# LCD_KEY.net
KiCad netlist of a schematic drawn in Altium Designer
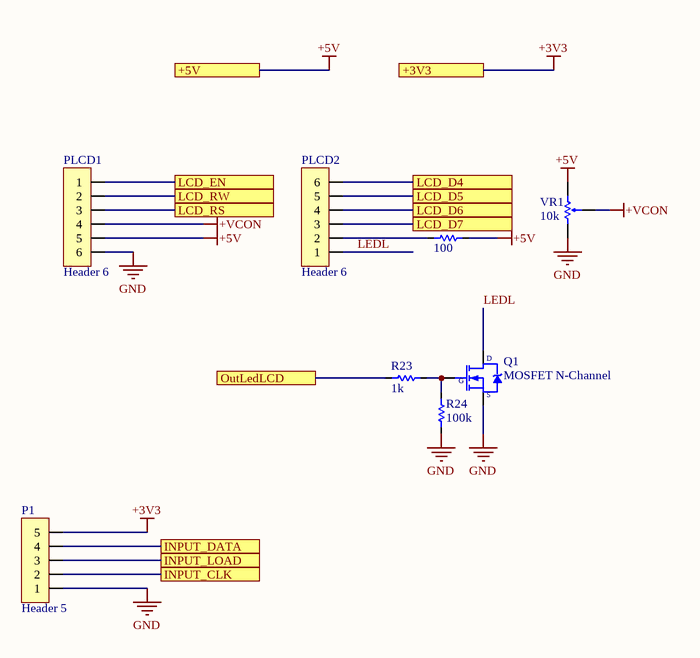
[diagram p0: LCD_KEY.SchDoc]

(export (version "E")
  (design (tool "Eeschema 10.0.6"))
  (components
    (comp (ref "P1")
      (value "Header 5")
      (footprint "Header 5")
      (description "Header, 5-Pin")
      (fields (field (name "PUBLISHER") "Altium Limited"))
      (libsource (lib "BKIT4U_LIB") (part "Header 5"))
    )
    (comp (ref "PLCD1")
      (value "Header 6")
      (footprint "XH2.54-6P")
      (description "Header, 6-Pin")
      (libsource (lib "BKIT4U_LIB_NEW") (part "Header 6"))
    )
    (comp (ref "PLCD2")
      (value "Header 6")
      (footprint "XH2.54-6P")
      (description "Header, 6-Pin")
      (libsource (lib "") (part "Header 6_1"))
    )
    (comp (ref "Q1")
      (value "MOSFET N-Channel")
      (footprint "SOT-23")
      (libsource (lib "BKIT4U_LIB_NEW") (part "MOSFET N-Channel"))
    )
    (comp (ref "R22")
      (value "100")
      (footprint "R 0603 (1608)")
      (description "Resistor")
      (fields (field (name "PUBLISHER") "Altium Limited"))
      (libsource (lib "BKIT4U_LIB_NEW") (part "Resistor"))
    )
    (comp (ref "R23")
      (value "1k")
      (footprint "R 0603 (1608)")
      (description "Resistor")
      (fields (field (name "PUBLISHER") "Altium Limited"))
      (libsource (lib "BKIT4U_LIB_NEW") (part "Resistor"))
    )
    (comp (ref "R24")
      (value "100k")
      (footprint "R 0603 (1608)")
      (description "Resistor")
      (fields (field (name "PUBLISHER") "Altium Limited"))
      (libsource (lib "BKIT4U_LIB_NEW") (part "Resistor"))
    )
    (comp (ref "VR1")
      (value "10k")
      (footprint "R VAR A")
      (description "Resistor Variable")
      (fields
        (field (name "MANUFACTURER") "Omron Automation and Safety")
        (field (name "MANUFACTURER PART NUMBER") "G3MB-202P DC5")
      )
      (libsource (lib "BKIT4U_LIB_NEW") (part "Resistor Variable"))
    )
  )
  (nets
    (net (code "1") (name "+3V3") (class "Default")
      (node (ref "P1") (pin "5") (pinfunction "5_5") (pintype "passive"))
    )
    (net (code "2") (name "+5V") (class "Default")
      (node (ref "PLCD1") (pin "5") (pinfunction "5_5") (pintype "passive"))
      (node (ref "R22") (pin "2") (pinfunction "2_2") (pintype "passive"))
      (node (ref "VR1") (pin "1") (pinfunction "1_1") (pintype "passive"))
    )
    (net (code "3") (name "+VCON") (class "Default")
      (node (ref "PLCD1") (pin "4") (pinfunction "4_4") (pintype "passive"))
      (node (ref "VR1") (pin "2") (pinfunction "2_2") (pintype "passive"))
    )
    (net (code "4") (name "/INPUT_CLK") (class "Default")
      (node (ref "P1") (pin "2") (pinfunction "2_2") (pintype "passive"))
    )
    (net (code "5") (name "/INPUT_DATA") (class "Default")
      (node (ref "P1") (pin "4") (pinfunction "4_4") (pintype "passive"))
    )
    (net (code "6") (name "/INPUT_LOAD") (class "Default")
      (node (ref "P1") (pin "3") (pinfunction "3_3") (pintype "passive"))
    )
    (net (code "7") (name "/LCD_D4") (class "Default")
      (node (ref "PLCD2") (pin "6") (pinfunction "6_6") (pintype "passive"))
    )
    (net (code "8") (name "/LCD_D5") (class "Default")
      (node (ref "PLCD2") (pin "5") (pinfunction "5_5") (pintype "passive"))
    )
    (net (code "9") (name "/LCD_D6") (class "Default")
      (node (ref "PLCD2") (pin "4") (pinfunction "4_4") (pintype "passive"))
    )
    (net (code "10") (name "/LCD_D7") (class "Default")
      (node (ref "PLCD2") (pin "3") (pinfunction "3_3") (pintype "passive"))
    )
    (net (code "11") (name "/LCD_EN") (class "Default")
      (node (ref "PLCD1") (pin "1") (pinfunction "1_1") (pintype "passive"))
    )
    (net (code "12") (name "/LCD_RS") (class "Default")
      (node (ref "PLCD1") (pin "3") (pinfunction "3_3") (pintype "passive"))
    )
    (net (code "13") (name "/LCD_RW") (class "Default")
      (node (ref "PLCD1") (pin "2") (pinfunction "2_2") (pintype "passive"))
    )
    (net (code "14") (name "/LEDL") (class "Default")
      (node (ref "PLCD2") (pin "1") (pinfunction "1_1") (pintype "passive"))
      (node (ref "Q1") (pin "3") (pinfunction "D_3") (pintype "passive"))
    )
    (net (code "15") (name "/OutLedLCD") (class "Default")
      (node (ref "R23") (pin "1") (pinfunction "1_1") (pintype "passive"))
    )
    (net (code "16") (name "GND") (class "Default")
      (node (ref "P1") (pin "1") (pinfunction "1_1") (pintype "passive"))
      (node (ref "PLCD1") (pin "6") (pinfunction "6_6") (pintype "passive"))
      (node (ref "Q1") (pin "2") (pinfunction "S_2") (pintype "passive"))
      (node (ref "R24") (pin "1") (pinfunction "1_1") (pintype "passive"))
      (node (ref "VR1") (pin "3") (pinfunction "3_3") (pintype "passive"))
    )
    (net (code "17") (name "Net-(PLCD2-Pad2)") (class "Default")
      (node (ref "PLCD2") (pin "2") (pinfunction "2_2") (pintype "passive"))
      (node (ref "R22") (pin "1") (pinfunction "1_1") (pintype "passive"))
    )
    (net (code "18") (name "Net-(Q1-G)") (class "Default")
      (node (ref "Q1") (pin "1") (pinfunction "G_1") (pintype "passive"))
      (node (ref "R23") (pin "2") (pinfunction "2_2") (pintype "passive"))
      (node (ref "R24") (pin "2") (pinfunction "2_2") (pintype "passive"))
    )
  )
)
